# Dogfish3D_-_Driver_Channel.net
KiCad netlist of a schematic drawn in Altium Designer
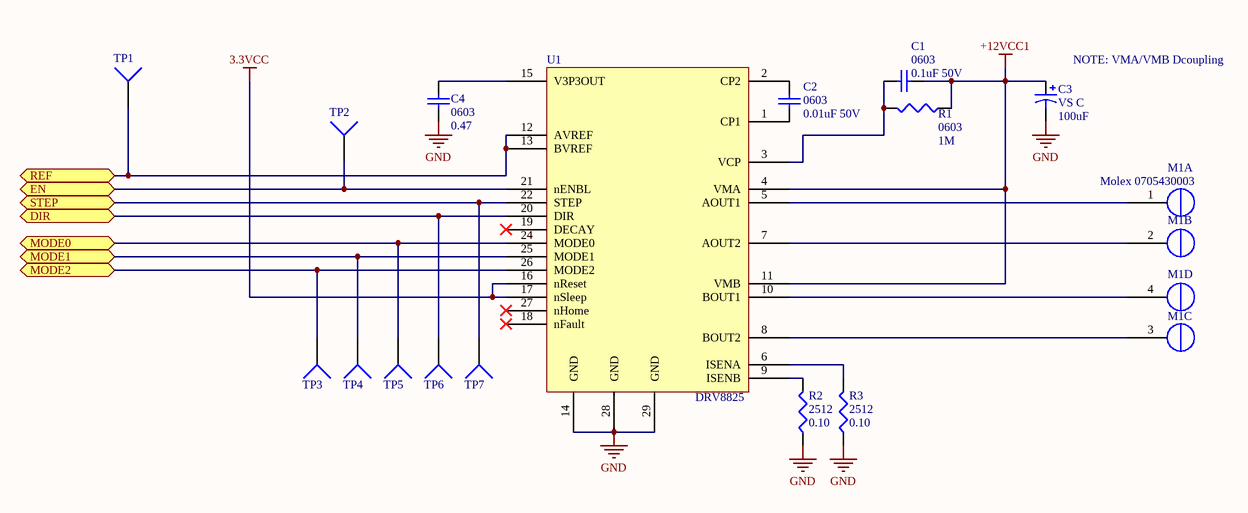
[diagram p0: Dogfish3D - Driver Channel.SchDoc]

(export (version "E")
  (design (tool "Eeschema 10.0.6"))
  (components
    (comp (ref "C1")
      (value "0603")
      (footprint "1608[0603]")
      (description "Capacitor (Semiconductor SIM Model)")
      (fields (field (name "ALTIUM_VALUE") "0.1uF 50V") (field (name "PUBLISHER") "Altium Limited"))
      (libsource (lib "Miscellaneous Devices") (part "Cap Semi"))
    )
    (comp (ref "C2")
      (value "0603")
      (footprint "1608[0603]")
      (description "Capacitor (Semiconductor SIM Model)")
      (fields (field (name "ALTIUM_VALUE") "0.01uF 50V") (field (name "PUBLISHER") "Altium Limited"))
      (libsource (lib "Miscellaneous Devices") (part "Cap Semi"))
    )
    (comp (ref "C3")
      (value "VS C")
      (footprint "Panasonic VS C")
      (description "Polarized Capacitor (Radial)")
      (fields (field (name "ALTIUM_VALUE") "100uF") (field (name "PUBLISHER") "Altium Limited"))
      (libsource (lib "Miscellaneous Devices") (part "Cap Pol1"))
    )
    (comp (ref "C4")
      (value "0603")
      (footprint "1608[0603]")
      (description "Capacitor (Semiconductor SIM Model)")
      (fields (field (name "ALTIUM_VALUE") "0.47") (field (name "PUBLISHER") "Altium Limited"))
      (libsource (lib "Miscellaneous Devices") (part "Cap Semi"))
    )
    (comp (ref "M1")
      (value "Molex 0705430003")
      (footprint "4POL254")
      (description "Molex 4 Pin Clip Connector")
      (libsource (lib "ZMBo Schematic Library") (part "Molex 0705430003 Alt"))
    )
    (comp (ref "R1")
      (value "0603")
      (footprint "J1-0603")
      (description "Resistor")
      (fields (field (name "ALTIUM_VALUE") "1M") (field (name "PUBLISHER") "Altium Limited"))
      (libsource (lib "Miscellaneous Devices") (part "Res3"))
    )
    (comp (ref "R2")
      (value "2512")
      (footprint "Resistor2512")
      (description "Resistor")
      (fields (field (name "ALTIUM_VALUE") "0.10") (field (name "PUBLISHER") "Altium Limited"))
      (libsource (lib "Miscellaneous Devices") (part "Res3"))
    )
    (comp (ref "R3")
      (value "2512")
      (footprint "Resistor2512")
      (description "Resistor")
      (fields (field (name "ALTIUM_VALUE") "0.10") (field (name "PUBLISHER") "Altium Limited"))
      (libsource (lib "Miscellaneous Devices") (part "Res3"))
    )
    (comp (ref "TP1")
      (value "TP4")
      (footprint "TP-2")
      (description "Socket")
      (fields (field (name "PUBLISHER") "Altium Limited"))
      (libsource (lib "ZMBo Schematic Library") (part "Socket"))
    )
    (comp (ref "TP2")
      (value "TP4")
      (footprint "TP-2")
      (description "Socket")
      (fields (field (name "PUBLISHER") "Altium Limited"))
      (libsource (lib "ZMBo Schematic Library") (part "Socket"))
    )
    (comp (ref "TP3")
      (value "TP4")
      (footprint "TP-2")
      (description "Socket")
      (fields (field (name "PUBLISHER") "Altium Limited"))
      (libsource (lib "ZMBo Schematic Library") (part "Socket"))
    )
    (comp (ref "TP4")
      (value "TP4")
      (footprint "TP-2")
      (description "Socket")
      (fields (field (name "PUBLISHER") "Altium Limited"))
      (libsource (lib "ZMBo Schematic Library") (part "Socket"))
    )
    (comp (ref "TP5")
      (value "TP4")
      (footprint "TP-2")
      (description "Socket")
      (fields (field (name "PUBLISHER") "Altium Limited"))
      (libsource (lib "ZMBo Schematic Library") (part "Socket"))
    )
    (comp (ref "TP6")
      (value "TP4")
      (footprint "TP-2")
      (description "Socket")
      (fields (field (name "PUBLISHER") "Altium Limited"))
      (libsource (lib "ZMBo Schematic Library") (part "Socket"))
    )
    (comp (ref "TP7")
      (value "TP4")
      (footprint "TP-2")
      (description "Socket")
      (fields (field (name "PUBLISHER") "Altium Limited"))
      (libsource (lib "ZMBo Schematic Library") (part "Socket"))
    )
    (comp (ref "U1")
      (value "DRV8825")
      (footprint "DRV8825")
      (description "DRV8825 Ti Stepper Driver")
      (libsource (lib "ZMBo Schematic Library") (part "DRV8825"))
    )
  )
  (nets
    (net (code "1") (name "+12VCC1") (class "Default")
      (node (ref "C1") (pin "1") (pinfunction "1_1") (pintype "passive"))
      (node (ref "C3") (pin "1") (pinfunction "1_1") (pintype "passive"))
      (node (ref "R1") (pin "1") (pinfunction "1_1") (pintype "passive"))
      (node (ref "U1") (pin "11") (pinfunction "VMB_11") (pintype "passive"))
      (node (ref "U1") (pin "4") (pinfunction "VMA_4") (pintype "passive"))
    )
    (net (code "2") (name "/DIR") (class "Default")
      (node (ref "TP6") (pin "1") (pinfunction "1_1") (pintype "passive"))
      (node (ref "U1") (pin "20") (pinfunction "DIR_20") (pintype "passive"))
    )
    (net (code "3") (name "/EN") (class "Default")
      (node (ref "TP2") (pin "1") (pinfunction "1_1") (pintype "passive"))
      (node (ref "U1") (pin "21") (pinfunction "nENBL_21") (pintype "passive"))
    )
    (net (code "4") (name "/MODE0") (class "Default")
      (node (ref "TP5") (pin "1") (pinfunction "1_1") (pintype "passive"))
      (node (ref "U1") (pin "24") (pinfunction "MODE0_24") (pintype "passive"))
    )
    (net (code "5") (name "/MODE1") (class "Default")
      (node (ref "TP4") (pin "1") (pinfunction "1_1") (pintype "passive"))
      (node (ref "U1") (pin "25") (pinfunction "MODE1_25") (pintype "passive"))
    )
    (net (code "6") (name "/MODE2") (class "Default")
      (node (ref "TP3") (pin "1") (pinfunction "1_1") (pintype "passive"))
      (node (ref "U1") (pin "26") (pinfunction "MODE2_26") (pintype "passive"))
    )
    (net (code "7") (name "/REF") (class "Default")
      (node (ref "TP1") (pin "1") (pinfunction "1_1") (pintype "passive"))
      (node (ref "U1") (pin "12") (pinfunction "AVREF_12") (pintype "passive"))
      (node (ref "U1") (pin "13") (pinfunction "BVREF_13") (pintype "passive"))
    )
    (net (code "8") (name "/STEP") (class "Default")
      (node (ref "TP7") (pin "1") (pinfunction "1_1") (pintype "passive"))
      (node (ref "U1") (pin "22") (pinfunction "STEP_22") (pintype "passive"))
    )
    (net (code "9") (name "3.3VCC") (class "Default")
      (node (ref "U1") (pin "16") (pinfunction "nReset_16") (pintype "passive"))
      (node (ref "U1") (pin "17") (pinfunction "nSleep_17") (pintype "passive"))
    )
    (net (code "10") (name "GND") (class "Default")
      (node (ref "C3") (pin "2") (pinfunction "2_2") (pintype "passive"))
      (node (ref "C4") (pin "1") (pinfunction "1_1") (pintype "passive"))
      (node (ref "R2") (pin "1") (pinfunction "1_1") (pintype "passive"))
      (node (ref "R3") (pin "1") (pinfunction "1_1") (pintype "passive"))
      (node (ref "U1") (pin "14") (pinfunction "GND_14") (pintype "passive"))
      (node (ref "U1") (pin "28") (pinfunction "GND_28") (pintype "passive"))
      (node (ref "U1") (pin "29") (pinfunction "GND_29") (pintype "passive"))
    )
    (net (code "11") (name "Net-(M1A-OUT2B)") (class "Default")
      (node (ref "M1") (pin "1") (pinfunction "OUT2B_1") (pintype "passive"))
      (node (ref "U1") (pin "5") (pinfunction "AOUT1_5") (pintype "passive"))
    )
    (net (code "12") (name "Net-(M1B-OUT2A)") (class "Default")
      (node (ref "M1") (pin "2") (pinfunction "OUT2A_2") (pintype "passive"))
      (node (ref "U1") (pin "7") (pinfunction "AOUT2_7") (pintype "passive"))
    )
    (net (code "13") (name "Net-(M1C-OUT1A)") (class "Default")
      (node (ref "M1") (pin "3") (pinfunction "OUT1A_3") (pintype "passive"))
      (node (ref "U1") (pin "8") (pinfunction "BOUT2_8") (pintype "passive"))
    )
    (net (code "14") (name "Net-(M1D-OUT1B)") (class "Default")
      (node (ref "M1") (pin "4") (pinfunction "OUT1B_4") (pintype "passive"))
      (node (ref "U1") (pin "10") (pinfunction "BOUT1_10") (pintype "passive"))
    )
    (net (code "15") (name "Net-(U1-CP1)") (class "Default")
      (node (ref "C2") (pin "1") (pinfunction "1_1") (pintype "passive"))
      (node (ref "U1") (pin "1") (pinfunction "CP1_1") (pintype "passive"))
    )
    (net (code "16") (name "Net-(U1-CP2)") (class "Default")
      (node (ref "C2") (pin "2") (pinfunction "2_2") (pintype "passive"))
      (node (ref "U1") (pin "2") (pinfunction "CP2_2") (pintype "passive"))
    )
    (net (code "17") (name "Net-(U1-ISENA)") (class "Default")
      (node (ref "R3") (pin "2") (pinfunction "2_2") (pintype "passive"))
      (node (ref "U1") (pin "6") (pinfunction "ISENA_6") (pintype "passive"))
    )
    (net (code "18") (name "Net-(U1-ISENB)") (class "Default")
      (node (ref "R2") (pin "2") (pinfunction "2_2") (pintype "passive"))
      (node (ref "U1") (pin "9") (pinfunction "ISENB_9") (pintype "passive"))
    )
    (net (code "19") (name "Net-(U1-V3P3OUT)") (class "Default")
      (node (ref "C4") (pin "2") (pinfunction "2_2") (pintype "passive"))
      (node (ref "U1") (pin "15") (pinfunction "V3P3OUT_15") (pintype "passive"))
    )
    (net (code "20") (name "Net-(U1-VCP)") (class "Default")
      (node (ref "C1") (pin "2") (pinfunction "2_2") (pintype "passive"))
      (node (ref "R1") (pin "2") (pinfunction "2_2") (pintype "passive"))
      (node (ref "U1") (pin "3") (pinfunction "VCP_3") (pintype "passive"))
    )
    (net (code "21") (name "unconnected-(U1-DECAY-Pad19)") (class "Default")
      (node (ref "U1") (pin "19") (pinfunction "DECAY_19") (pintype "passive+no_connect"))
    )
    (net (code "22") (name "unconnected-(U1-NC-Pad23)") (class "Default")
      (node (ref "U1") (pin "23") (pinfunction "NC_23") (pintype "passive"))
    )
    (net (code "23") (name "unconnected-(U1-nFault-Pad18)") (class "Default")
      (node (ref "U1") (pin "18") (pinfunction "nFault_18") (pintype "passive+no_connect"))
    )
    (net (code "24") (name "unconnected-(U1-nHome-Pad27)") (class "Default")
      (node (ref "U1") (pin "27") (pinfunction "nHome_27") (pintype "passive+no_connect"))
    )
  )
)
